# RP2350A.net
KiCad netlist of a schematic drawn in Altium Designer
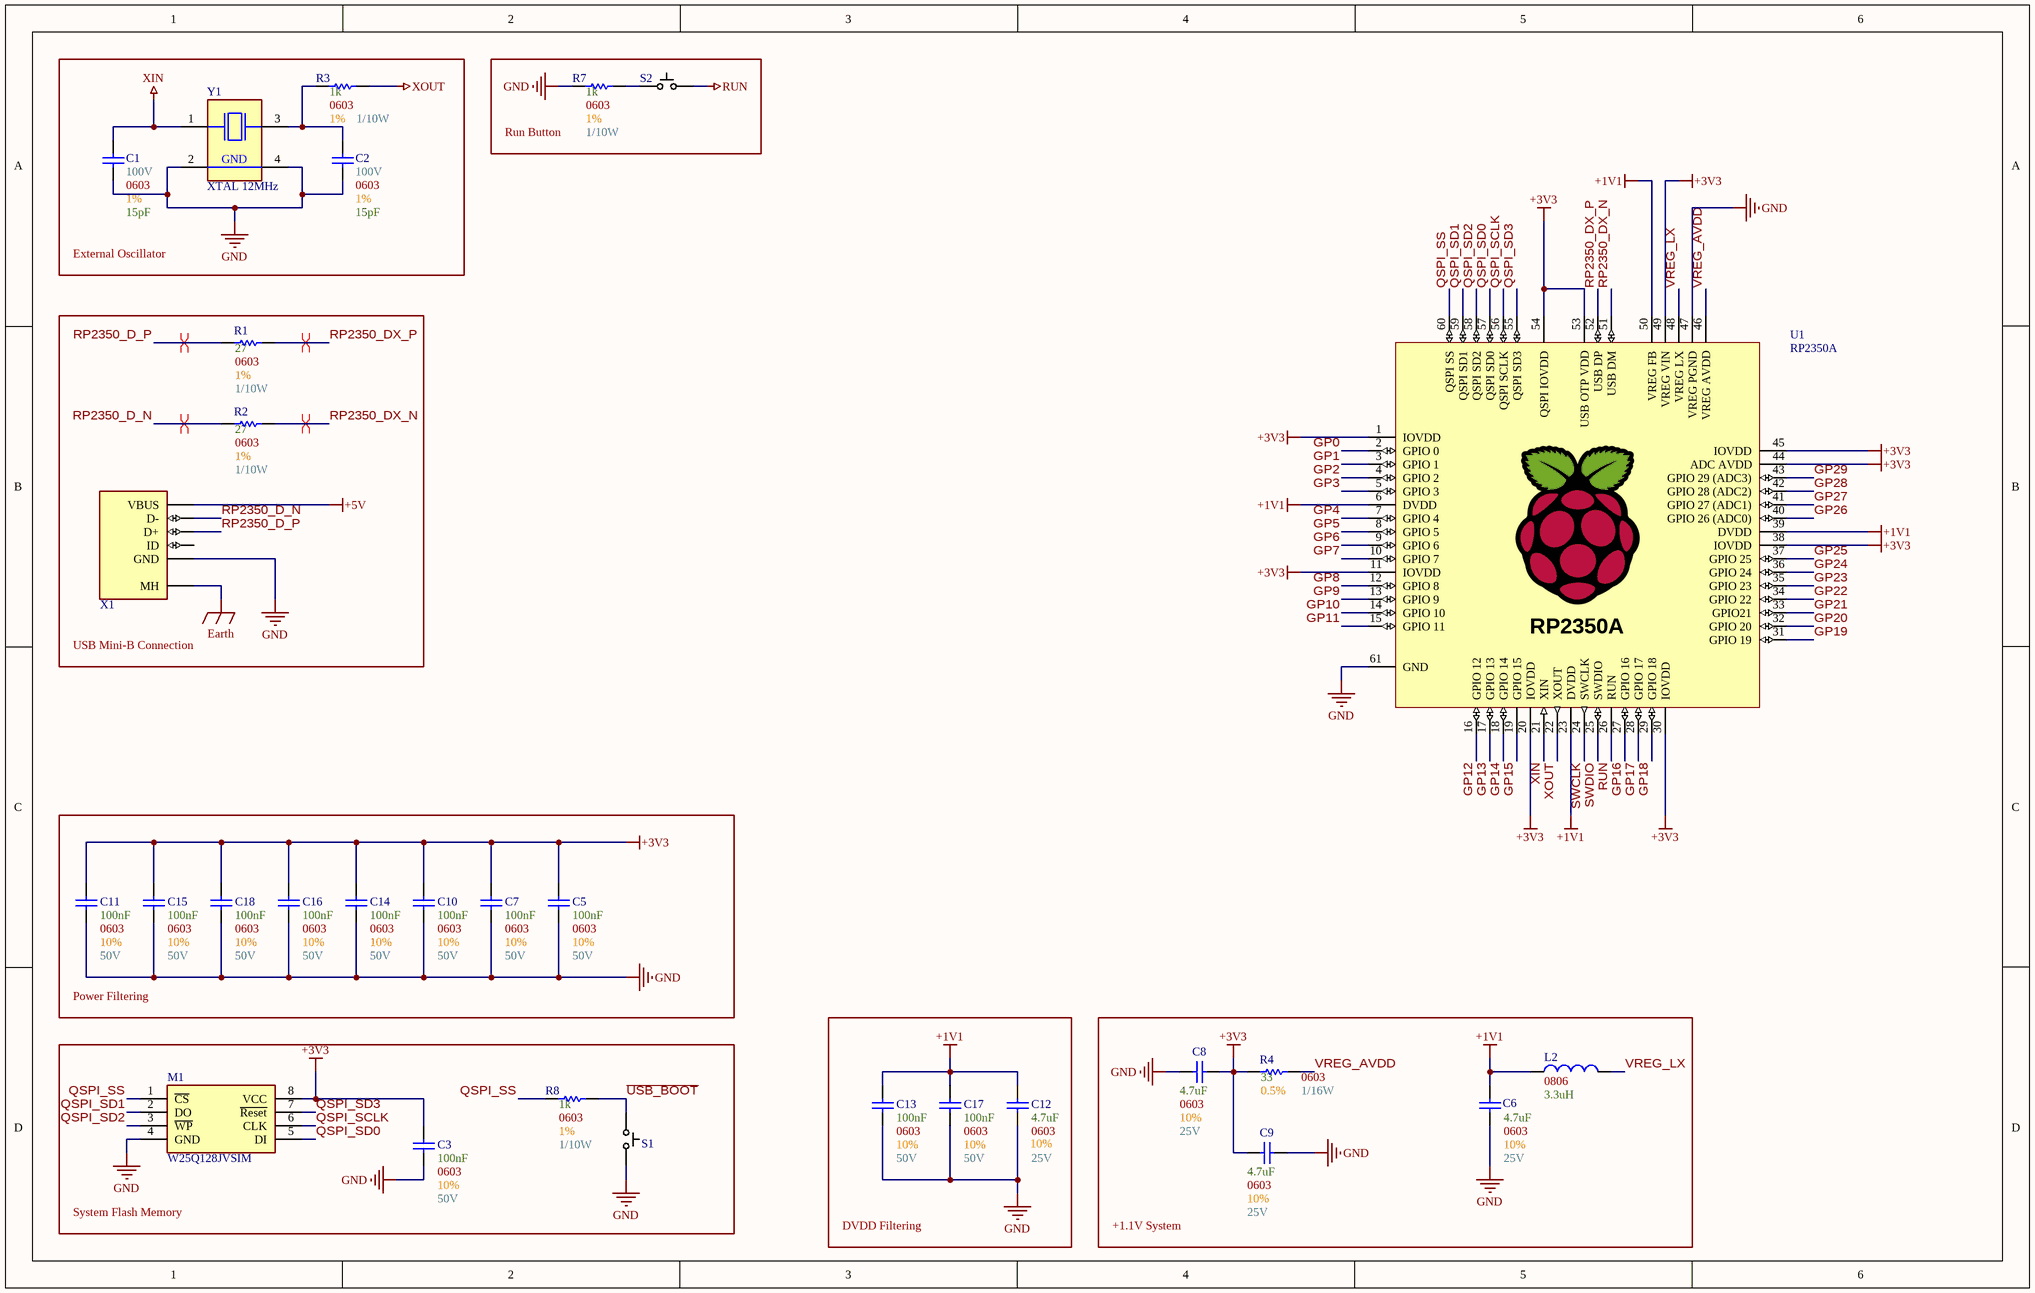
[diagram p0: RP2350A.SchDoc]

(export (version "E")
  (design (tool "Eeschema 10.0.6"))
  (components
    (comp (ref "C1")
      (value "[Cap] 0603 15pF 1% 100V")
      (footprint "[Cap] SMD 0603")
      (description "GCM1885C2A150FA16D")
      (fields
        (field (name "MAX VOLTAGE") "100V")
        (field (name "SIZE PACKAGE") "0603")
        (field (name "TOLERANCE") "1%")
        (field (name "CAPACITANCE") "15pF")
      )
      (libsource (lib "Capacitors") (part "[Cap] 0603 15pF 1% 100V"))
    )
    (comp (ref "C2")
      (value "[Cap] 0603 15pF 1% 100V")
      (footprint "[Cap] SMD 0603")
      (description "GCM1885C2A150FA16D")
      (fields
        (field (name "MAX VOLTAGE") "100V")
        (field (name "SIZE PACKAGE") "0603")
        (field (name "TOLERANCE") "1%")
        (field (name "CAPACITANCE") "15pF")
      )
      (libsource (lib "Capacitors") (part "[Cap] 0603 15pF 1% 100V"))
    )
    (comp (ref "C3")
      (value "[Cap] 0603 0.1uF 10% 50V")
      (footprint "[Cap] SMD 0603")
      (description "CL10B104KB8NNNC")
      (fields
        (field (name "MAX VOLTAGE") "50V")
        (field (name "SIZE PACKAGE") "0603")
        (field (name "TOLERANCE") "10%")
        (field (name "CAPACITANCE") "100nF")
      )
      (libsource (lib "Capacitors") (part "[Cap] 0603 0.1uF 10% 50V"))
    )
    (comp (ref "C5")
      (value "[Cap] 0603 0.1uF 10% 50V")
      (footprint "[Cap] SMD 0603")
      (description "CL10B104KB8NNNC")
      (fields
        (field (name "MAX VOLTAGE") "50V")
        (field (name "SIZE PACKAGE") "0603")
        (field (name "TOLERANCE") "10%")
        (field (name "CAPACITANCE") "100nF")
      )
      (libsource (lib "Capacitors") (part "[Cap] 0603 0.1uF 10% 50V"))
    )
    (comp (ref "C6")
      (value "[Cap] 0603 4.7uF 10% 25V")
      (footprint "[Cap] SMD 0603")
      (description "GRM188R61E475KE11D")
      (fields
        (field (name "MAX VOLTAGE") "25V")
        (field (name "SIZE PACKAGE") "0603")
        (field (name "TOLERANCE") "10%")
        (field (name "CAPACITANCE") "4.7uF")
      )
      (libsource (lib "Capacitors") (part "[Cap] 0603 4.7uF 10% 25V"))
    )
    (comp (ref "C7")
      (value "[Cap] 0603 0.1uF 10% 50V")
      (footprint "[Cap] SMD 0603")
      (description "CL10B104KB8NNNC")
      (fields
        (field (name "MAX VOLTAGE") "50V")
        (field (name "SIZE PACKAGE") "0603")
        (field (name "TOLERANCE") "10%")
        (field (name "CAPACITANCE") "100nF")
      )
      (libsource (lib "Capacitors") (part "[Cap] 0603 0.1uF 10% 50V"))
    )
    (comp (ref "C8")
      (value "[Cap] 0603 4.7uF 10% 25V")
      (footprint "[Cap] SMD 0603")
      (description "GRM188R61E475KE11D")
      (fields
        (field (name "MAX VOLTAGE") "25V")
        (field (name "SIZE PACKAGE") "0603")
        (field (name "TOLERANCE") "10%")
        (field (name "CAPACITANCE") "4.7uF")
      )
      (libsource (lib "Capacitors") (part "[Cap] 0603 4.7uF 10% 25V"))
    )
    (comp (ref "C9")
      (value "[Cap] 0603 4.7uF 10% 25V")
      (footprint "[Cap] SMD 0603")
      (description "GRM188R61E475KE11D")
      (fields
        (field (name "MAX VOLTAGE") "25V")
        (field (name "SIZE PACKAGE") "0603")
        (field (name "TOLERANCE") "10%")
        (field (name "CAPACITANCE") "4.7uF")
      )
      (libsource (lib "Capacitors") (part "[Cap] 0603 4.7uF 10% 25V"))
    )
    (comp (ref "C10")
      (value "[Cap] 0603 0.1uF 10% 50V")
      (footprint "[Cap] SMD 0603")
      (description "CL10B104KB8NNNC")
      (fields
        (field (name "MAX VOLTAGE") "50V")
        (field (name "SIZE PACKAGE") "0603")
        (field (name "TOLERANCE") "10%")
        (field (name "CAPACITANCE") "100nF")
      )
      (libsource (lib "Capacitors") (part "[Cap] 0603 0.1uF 10% 50V"))
    )
    (comp (ref "C11")
      (value "[Cap] 0603 0.1uF 10% 50V")
      (footprint "[Cap] SMD 0603")
      (description "CL10B104KB8NNNC")
      (fields
        (field (name "MAX VOLTAGE") "50V")
        (field (name "SIZE PACKAGE") "0603")
        (field (name "TOLERANCE") "10%")
        (field (name "CAPACITANCE") "100nF")
      )
      (libsource (lib "Capacitors") (part "[Cap] 0603 0.1uF 10% 50V"))
    )
    (comp (ref "C12")
      (value "[Cap] 0603 4.7uF 10% 25V")
      (footprint "[Cap] SMD 0603")
      (description "GRM188R61E475KE11D")
      (fields
        (field (name "MAX VOLTAGE") "25V")
        (field (name "SIZE PACKAGE") "0603")
        (field (name "TOLERANCE") "10%")
        (field (name "CAPACITANCE") "4.7uF")
      )
      (libsource (lib "Capacitors") (part "[Cap] 0603 4.7uF 10% 25V"))
    )
    (comp (ref "C13")
      (value "[Cap] 0603 0.1uF 10% 50V")
      (footprint "[Cap] SMD 0603")
      (description "CL10B104KB8NNNC")
      (fields
        (field (name "MAX VOLTAGE") "50V")
        (field (name "SIZE PACKAGE") "0603")
        (field (name "TOLERANCE") "10%")
        (field (name "CAPACITANCE") "100nF")
      )
      (libsource (lib "Capacitors") (part "[Cap] 0603 0.1uF 10% 50V"))
    )
    (comp (ref "C14")
      (value "[Cap] 0603 0.1uF 10% 50V")
      (footprint "[Cap] SMD 0603")
      (description "CL10B104KB8NNNC")
      (fields
        (field (name "MAX VOLTAGE") "50V")
        (field (name "SIZE PACKAGE") "0603")
        (field (name "TOLERANCE") "10%")
        (field (name "CAPACITANCE") "100nF")
      )
      (libsource (lib "Capacitors") (part "[Cap] 0603 0.1uF 10% 50V"))
    )
    (comp (ref "C15")
      (value "[Cap] 0603 0.1uF 10% 50V")
      (footprint "[Cap] SMD 0603")
      (description "CL10B104KB8NNNC")
      (fields
        (field (name "MAX VOLTAGE") "50V")
        (field (name "SIZE PACKAGE") "0603")
        (field (name "TOLERANCE") "10%")
        (field (name "CAPACITANCE") "100nF")
      )
      (libsource (lib "Capacitors") (part "[Cap] 0603 0.1uF 10% 50V"))
    )
    (comp (ref "C16")
      (value "[Cap] 0603 0.1uF 10% 50V")
      (footprint "[Cap] SMD 0603")
      (description "CL10B104KB8NNNC")
      (fields
        (field (name "MAX VOLTAGE") "50V")
        (field (name "SIZE PACKAGE") "0603")
        (field (name "TOLERANCE") "10%")
        (field (name "CAPACITANCE") "100nF")
      )
      (libsource (lib "Capacitors") (part "[Cap] 0603 0.1uF 10% 50V"))
    )
    (comp (ref "C17")
      (value "[Cap] 0603 0.1uF 10% 50V")
      (footprint "[Cap] SMD 0603")
      (description "CL10B104KB8NNNC")
      (fields
        (field (name "MAX VOLTAGE") "50V")
        (field (name "SIZE PACKAGE") "0603")
        (field (name "TOLERANCE") "10%")
        (field (name "CAPACITANCE") "100nF")
      )
      (libsource (lib "Capacitors") (part "[Cap] 0603 0.1uF 10% 50V"))
    )
    (comp (ref "C18")
      (value "[Cap] 0603 0.1uF 10% 50V")
      (footprint "[Cap] SMD 0603")
      (description "CL10B104KB8NNNC")
      (fields
        (field (name "MAX VOLTAGE") "50V")
        (field (name "SIZE PACKAGE") "0603")
        (field (name "TOLERANCE") "10%")
        (field (name "CAPACITANCE") "100nF")
      )
      (libsource (lib "Capacitors") (part "[Cap] 0603 0.1uF 10% 50V"))
    )
    (comp (ref "L2")
      (value "[3.3uH] SMD 0806 2.1A")
      (footprint "[Inductor] SMD 0806")
      (description "AOTA-B201610S3R3-101-T")
      (fields (field (name "PACKAGE") "0806") (field (name "INDUCTANCE") "3.3uH"))
      (libsource (lib "Inductors") (part "[3.3uH] SMD 0806 2.1A"))
    )
    (comp (ref "M1")
      (value "W25Q128JVSIM")
      (footprint "[Flash] 128MBit")
      (libsource (lib "Memory") (part "[Flash] 128MBit"))
    )
    (comp (ref "R1")
      (value "[27] SMD 0603 1% 1/10W")
      (footprint "[Res] SMD 0603")
      (description "MCT06030C2709FP500")
      (fields
        (field (name "WATTAGE") "1/10W")
        (field (name "TOLERANCE") "1%")
        (field (name "RESISTANCE") "27")
        (field (name "SIZE PACKAGE") "0603")
      )
      (libsource (lib "Resistors") (part "[27] SMD 0603 1% 1/10W"))
    )
    (comp (ref "R2")
      (value "[27] SMD 0603 1% 1/10W")
      (footprint "[Res] SMD 0603")
      (description "MCT06030C2709FP500")
      (fields
        (field (name "WATTAGE") "1/10W")
        (field (name "TOLERANCE") "1%")
        (field (name "RESISTANCE") "27")
        (field (name "SIZE PACKAGE") "0603")
      )
      (libsource (lib "Resistors") (part "[27] SMD 0603 1% 1/10W"))
    )
    (comp (ref "R3")
      (value "[1k] SMD 0603 1% 1/10W")
      (footprint "[Res] SMD 0603")
      (description "RMCF0603FT1K00")
      (fields
        (field (name "WATTAGE") "1/10W")
        (field (name "TOLERANCE") "1%")
        (field (name "RESISTANCE") "1k")
        (field (name "SIZE PACKAGE") "0603")
      )
      (libsource (lib "Resistors") (part "[1k] SMD 0603 1% 1/10W"))
    )
    (comp (ref "R4")
      (value "[33] SMD 0603 0.5% 1/16W")
      (footprint "[Res] SMD 0603")
      (description "RR0816Q-330-D")
      (fields
        (field (name "WATTAGE") "1/16W")
        (field (name "TOLERANCE") "0.5%")
        (field (name "RESISTANCE") "33")
        (field (name "SIZE PACKAGE") "0603")
      )
      (libsource (lib "Resistors") (part "[33] SMD 0603 0.5% 1/16W"))
    )
    (comp (ref "R7")
      (value "[1k] SMD 0603 1% 1/10W")
      (footprint "[Res] SMD 0603")
      (description "RMCF0603FT1K00")
      (fields
        (field (name "WATTAGE") "1/10W")
        (field (name "TOLERANCE") "1%")
        (field (name "RESISTANCE") "1k")
        (field (name "SIZE PACKAGE") "0603")
      )
      (libsource (lib "Resistors") (part "[1k] SMD 0603 1% 1/10W"))
    )
    (comp (ref "R8")
      (value "[1k] SMD 0603 1% 1/10W")
      (footprint "[Res] SMD 0603")
      (description "RMCF0603FT1K00")
      (fields
        (field (name "WATTAGE") "1/10W")
        (field (name "TOLERANCE") "1%")
        (field (name "RESISTANCE") "1k")
        (field (name "SIZE PACKAGE") "0603")
      )
      (libsource (lib "Resistors") (part "[1k] SMD 0603 1% 1/10W"))
    )
    (comp (ref "S1")
      (value "[SPST] SMD Pushbutton")
      (footprint "[SPST] SMD Pushbutton")
      (description "PTS815SJM250SMTRLFS")
      (libsource (lib "Switches") (part "[SPST] SMD Pushbutton"))
    )
    (comp (ref "S2")
      (value "[SPST] SMD Pushbutton")
      (footprint "[SPST] SMD Pushbutton")
      (description "PTS815SJM250SMTRLFS")
      (libsource (lib "Switches") (part "[SPST] SMD Pushbutton"))
    )
    (comp (ref "U1")
      (value "RP2350A")
      (footprint "[MCU] RP2350A")
      (description "QFN-60 Package")
      (libsource (lib "MCUs") (part "[MCU] RP2350A"))
    )
    (comp (ref "X1")
      (value "[USB] Type-B Mini")
      (footprint "[USB] Type-B Mini")
      (description "MUSB-05-S-B-SM-A-K-TR")
      (libsource (lib "Connectors") (part "[USB] Type-B Mini"))
    )
    (comp (ref "Y1")
      (value "XTAL 12MHz")
      (footprint "[Crystal] SMD 12MHz")
      (description "815-ABM8-272-T3")
      (libsource (lib "Crystals and Oscillators") (part "[Crystal] SMD 12MHz"))
    )
  )
  (nets
    (net (code "1") (name "+1V1") (class "Default")
      (node (ref "C12") (pin "2") (pinfunction "2_2") (pintype "passive"))
      (node (ref "C13") (pin "2") (pinfunction "2_2") (pintype "passive"))
      (node (ref "C17") (pin "2") (pinfunction "2_2") (pintype "passive"))
      (node (ref "C6") (pin "1") (pinfunction "1_1") (pintype "passive"))
      (node (ref "L2") (pin "1") (pinfunction "1_1") (pintype "passive"))
      (node (ref "U1") (pin "23") (pinfunction "DVDD_23") (pintype "power_in"))
      (node (ref "U1") (pin "39") (pinfunction "DVDD_39") (pintype "power_in"))
      (node (ref "U1") (pin "50") (pinfunction "VREG_FB_50") (pintype "power_in"))
      (node (ref "U1") (pin "6") (pinfunction "DVDD_6") (pintype "power_in"))
    )
    (net (code "2") (name "+3V3") (class "Default")
      (node (ref "C10") (pin "2") (pinfunction "2_2") (pintype "passive"))
      (node (ref "C11") (pin "2") (pinfunction "2_2") (pintype "passive"))
      (node (ref "C14") (pin "2") (pinfunction "2_2") (pintype "passive"))
      (node (ref "C15") (pin "2") (pinfunction "2_2") (pintype "passive"))
      (node (ref "C16") (pin "2") (pinfunction "2_2") (pintype "passive"))
      (node (ref "C18") (pin "2") (pinfunction "2_2") (pintype "passive"))
      (node (ref "C3") (pin "2") (pinfunction "2_2") (pintype "passive"))
      (node (ref "C5") (pin "2") (pinfunction "2_2") (pintype "passive"))
      (node (ref "C7") (pin "2") (pinfunction "2_2") (pintype "passive"))
      (node (ref "C8") (pin "1") (pinfunction "1_1") (pintype "passive"))
      (node (ref "C9") (pin "2") (pinfunction "2_2") (pintype "passive"))
      (node (ref "M1") (pin "8") (pinfunction "VCC_8") (pintype "passive"))
      (node (ref "R4") (pin "1") (pinfunction "1_1") (pintype "passive"))
      (node (ref "U1") (pin "1") (pinfunction "IOVDD_1") (pintype "power_in"))
      (node (ref "U1") (pin "11") (pinfunction "IOVDD_11") (pintype "power_in"))
      (node (ref "U1") (pin "20") (pinfunction "IOVDD_20") (pintype "power_in"))
      (node (ref "U1") (pin "30") (pinfunction "IOVDD_30") (pintype "power_in"))
      (node (ref "U1") (pin "38") (pinfunction "IOVDD_38") (pintype "power_in"))
      (node (ref "U1") (pin "44") (pinfunction "ADC_AVDD_44") (pintype "power_in"))
      (node (ref "U1") (pin "45") (pinfunction "IOVDD_45") (pintype "power_in"))
      (node (ref "U1") (pin "49") (pinfunction "VREG_VIN_49") (pintype "power_in"))
      (node (ref "U1") (pin "53") (pinfunction "USB_OTP_VDD_53") (pintype "power_in"))
      (node (ref "U1") (pin "54") (pinfunction "QSPI_IOVDD_54") (pintype "power_in"))
    )
    (net (code "3") (name "+5V") (class "Default")
      (node (ref "X1") (pin "1") (pinfunction "VBUS_1") (pintype "power_in"))
    )
    (net (code "4") (name "/GP0") (class "Default")
      (node (ref "U1") (pin "2") (pinfunction "GPIO_0_2") (pintype "bidirectional"))
    )
    (net (code "5") (name "/GP1") (class "Default")
      (node (ref "U1") (pin "3") (pinfunction "GPIO_1_3") (pintype "bidirectional"))
    )
    (net (code "6") (name "/GP2") (class "Default")
      (node (ref "U1") (pin "4") (pinfunction "GPIO_2_4") (pintype "bidirectional"))
    )
    (net (code "7") (name "/GP3") (class "Default")
      (node (ref "U1") (pin "5") (pinfunction "GPIO_3_5") (pintype "bidirectional"))
    )
    (net (code "8") (name "/GP4") (class "Default")
      (node (ref "U1") (pin "7") (pinfunction "GPIO_4_7") (pintype "bidirectional"))
    )
    (net (code "9") (name "/GP5") (class "Default")
      (node (ref "U1") (pin "8") (pinfunction "GPIO_5_8") (pintype "bidirectional"))
    )
    (net (code "10") (name "/GP6") (class "Default")
      (node (ref "U1") (pin "9") (pinfunction "GPIO_6_9") (pintype "bidirectional"))
    )
    (net (code "11") (name "/GP7") (class "Default")
      (node (ref "U1") (pin "10") (pinfunction "GPIO_7_10") (pintype "bidirectional"))
    )
    (net (code "12") (name "/GP8") (class "Default")
      (node (ref "U1") (pin "12") (pinfunction "GPIO_8_12") (pintype "bidirectional"))
    )
    (net (code "13") (name "/GP9") (class "Default")
      (node (ref "U1") (pin "13") (pinfunction "GPIO_9_13") (pintype "bidirectional"))
    )
    (net (code "14") (name "/GP10") (class "Default")
      (node (ref "U1") (pin "14") (pinfunction "GPIO_10_14") (pintype "bidirectional"))
    )
    (net (code "15") (name "/GP11") (class "Default")
      (node (ref "U1") (pin "15") (pinfunction "GPIO_11_15") (pintype "bidirectional"))
    )
    (net (code "16") (name "/GP12") (class "Default")
      (node (ref "U1") (pin "16") (pinfunction "GPIO_12_16") (pintype "bidirectional"))
    )
    (net (code "17") (name "/GP13") (class "Default")
      (node (ref "U1") (pin "17") (pinfunction "GPIO_13_17") (pintype "bidirectional"))
    )
    (net (code "18") (name "/GP14") (class "Default")
      (node (ref "U1") (pin "18") (pinfunction "GPIO_14_18") (pintype "bidirectional"))
    )
    (net (code "19") (name "/GP15") (class "Default")
      (node (ref "U1") (pin "19") (pinfunction "GPIO_15_19") (pintype "power_in"))
    )
    (net (code "20") (name "/GP16") (class "Default")
      (node (ref "U1") (pin "27") (pinfunction "GPIO_16_27") (pintype "bidirectional"))
    )
    (net (code "21") (name "/GP17") (class "Default")
      (node (ref "U1") (pin "28") (pinfunction "GPIO_17_28") (pintype "bidirectional"))
    )
    (net (code "22") (name "/GP18") (class "Default")
      (node (ref "U1") (pin "29") (pinfunction "GPIO_18_29") (pintype "bidirectional"))
    )
    (net (code "23") (name "/GP19") (class "Default")
      (node (ref "U1") (pin "31") (pinfunction "GPIO_19_31") (pintype "bidirectional"))
    )
    (net (code "24") (name "/GP20") (class "Default")
      (node (ref "U1") (pin "32") (pinfunction "GPIO_20_32") (pintype "bidirectional"))
    )
    (net (code "25") (name "/GP21") (class "Default")
      (node (ref "U1") (pin "33") (pinfunction "GPIO21_33") (pintype "bidirectional"))
    )
    (net (code "26") (name "/GP22") (class "Default")
      (node (ref "U1") (pin "34") (pinfunction "GPIO_22_34") (pintype "bidirectional"))
    )
    (net (code "27") (name "/GP23") (class "Default")
      (node (ref "U1") (pin "35") (pinfunction "GPIO_23_35") (pintype "bidirectional"))
    )
    (net (code "28") (name "/GP24") (class "Default")
      (node (ref "U1") (pin "36") (pinfunction "GPIO_24_36") (pintype "bidirectional"))
    )
    (net (code "29") (name "/GP25") (class "Default")
      (node (ref "U1") (pin "37") (pinfunction "GPIO_25_37") (pintype "bidirectional"))
    )
    (net (code "30") (name "/GP26") (class "Default")
      (node (ref "U1") (pin "40") (pinfunction "GPIO_26_(ADC0)_40") (pintype "bidirectional"))
    )
    (net (code "31") (name "/GP27") (class "Default")
      (node (ref "U1") (pin "41") (pinfunction "GPIO_27_(ADC1)_41") (pintype "bidirectional"))
    )
    (net (code "32") (name "/GP28") (class "Default")
      (node (ref "U1") (pin "42") (pinfunction "GPIO_28_(ADC2)_42") (pintype "bidirectional"))
    )
    (net (code "33") (name "/GP29") (class "Default")
      (node (ref "U1") (pin "43") (pinfunction "GPIO_29_(ADC3)_43") (pintype "bidirectional"))
    )
    (net (code "34") (name "/QSPI_SCLK") (class "Default")
      (node (ref "M1") (pin "6") (pinfunction "CLK_6") (pintype "passive"))
      (node (ref "U1") (pin "56") (pinfunction "QSPI_SCLK_56") (pintype "bidirectional"))
    )
    (net (code "35") (name "/QSPI_SD0") (class "Default")
      (node (ref "M1") (pin "5") (pinfunction "DI_5") (pintype "passive"))
      (node (ref "U1") (pin "57") (pinfunction "QSPI_SD0_57") (pintype "bidirectional"))
    )
    (net (code "36") (name "/QSPI_SD1") (class "Default")
      (node (ref "M1") (pin "2") (pinfunction "DO_2") (pintype "passive"))
      (node (ref "U1") (pin "59") (pinfunction "QSPI_SD1_59") (pintype "bidirectional"))
    )
    (net (code "37") (name "/QSPI_SD2") (class "Default")
      (node (ref "M1") (pin "3") (pinfunction "~{WP}_3") (pintype "passive"))
      (node (ref "U1") (pin "58") (pinfunction "QSPI_SD2_58") (pintype "bidirectional"))
    )
    (net (code "38") (name "/QSPI_SD3") (class "Default")
      (node (ref "M1") (pin "7") (pinfunction "~{Reset}_7") (pintype "passive"))
      (node (ref "U1") (pin "55") (pinfunction "QSPI_SD3_55") (pintype "bidirectional"))
    )
    (net (code "39") (name "/QSPI_SS") (class "Default")
      (node (ref "M1") (pin "1") (pinfunction "~{CS}_1") (pintype "passive"))
      (node (ref "R8") (pin "1") (pinfunction "1_1") (pintype "passive"))
      (node (ref "U1") (pin "60") (pinfunction "QSPI_SS_60") (pintype "bidirectional"))
    )
    (net (code "40") (name "/RP2350_DX_N") (class "Default")
      (node (ref "R2") (pin "2") (pinfunction "2_2") (pintype "passive"))
      (node (ref "U1") (pin "51") (pinfunction "USB_DM_51") (pintype "bidirectional"))
    )
    (net (code "41") (name "/RP2350_DX_P") (class "Default")
      (node (ref "R1") (pin "2") (pinfunction "2_2") (pintype "passive"))
      (node (ref "U1") (pin "52") (pinfunction "USB_DP_52") (pintype "bidirectional"))
    )
    (net (code "42") (name "/RP2350_D_N") (class "Default")
      (node (ref "R2") (pin "1") (pinfunction "1_1") (pintype "passive"))
      (node (ref "X1") (pin "2") (pinfunction "D-_2") (pintype "bidirectional"))
    )
    (net (code "43") (name "/RP2350_D_P") (class "Default")
      (node (ref "R1") (pin "1") (pinfunction "1_1") (pintype "passive"))
      (node (ref "X1") (pin "3") (pinfunction "D+_3") (pintype "bidirectional"))
    )
    (net (code "44") (name "/SWCLK") (class "Default")
      (node (ref "U1") (pin "24") (pinfunction "SWCLK_24") (pintype "output"))
    )
    (net (code "45") (name "/SWDIO") (class "Default")
      (node (ref "U1") (pin "25") (pinfunction "SWDIO_25") (pintype "bidirectional"))
    )
    (net (code "46") (name "/VREG_AVDD") (class "Default")
      (node (ref "R4") (pin "2") (pinfunction "2_2") (pintype "passive"))
      (node (ref "U1") (pin "46") (pinfunction "VREG_AVDD_46") (pintype "power_in"))
    )
    (net (code "47") (name "/VREG_LX") (class "Default")
      (node (ref "L2") (pin "2") (pinfunction "2_2") (pintype "passive"))
      (node (ref "U1") (pin "48") (pinfunction "VREG_LX_48") (pintype "power_in"))
    )
    (net (code "48") (name "/~{USB_BOOT}") (class "Default")
      (node (ref "R8") (pin "2") (pinfunction "2_2") (pintype "passive"))
      (node (ref "S1") (pin "1") (pintype "power_in"))
    )
    (net (code "49") (name "Earth") (class "Default")
      (node (ref "X1") (pin "MH") (pinfunction "MH_MH") (pintype "power_in"))
    )
    (net (code "50") (name "GND") (class "Default")
      (node (ref "C1") (pin "1") (pinfunction "1_1") (pintype "passive"))
      (node (ref "C10") (pin "1") (pinfunction "1_1") (pintype "passive"))
      (node (ref "C11") (pin "1") (pinfunction "1_1") (pintype "passive"))
      (node (ref "C12") (pin "1") (pinfunction "1_1") (pintype "passive"))
      (node (ref "C13") (pin "1") (pinfunction "1_1") (pintype "passive"))
      (node (ref "C14") (pin "1") (pinfunction "1_1") (pintype "passive"))
      (node (ref "C15") (pin "1") (pinfunction "1_1") (pintype "passive"))
      (node (ref "C16") (pin "1") (pinfunction "1_1") (pintype "passive"))
      (node (ref "C17") (pin "1") (pinfunction "1_1") (pintype "passive"))
      (node (ref "C18") (pin "1") (pinfunction "1_1") (pintype "passive"))
      (node (ref "C2") (pin "1") (pinfunction "1_1") (pintype "passive"))
      (node (ref "C3") (pin "1") (pinfunction "1_1") (pintype "passive"))
      (node (ref "C5") (pin "1") (pinfunction "1_1") (pintype "passive"))
      (node (ref "C6") (pin "2") (pinfunction "2_2") (pintype "passive"))
      (node (ref "C7") (pin "1") (pinfunction "1_1") (pintype "passive"))
      (node (ref "C8") (pin "2") (pinfunction "2_2") (pintype "passive"))
      (node (ref "C9") (pin "1") (pinfunction "1_1") (pintype "passive"))
      (node (ref "M1") (pin "4") (pinfunction "GND_4") (pintype "passive"))
      (node (ref "R7") (pin "1") (pinfunction "1_1") (pintype "passive"))
      (node (ref "S1") (pin "2") (pintype "power_in"))
      (node (ref "U1") (pin "47") (pinfunction "VREG_PGND_47") (pintype "power_in"))
      (node (ref "U1") (pin "61") (pinfunction "GND_61") (pintype "power_in"))
      (node (ref "X1") (pin "5") (pinfunction "GND_5") (pintype "power_in"))
      (node (ref "Y1") (pin "2") (pinfunction "GND_2") (pintype "power_in"))
      (node (ref "Y1") (pin "4") (pinfunction "GND_4") (pintype "power_in"))
    )
    (net (code "51") (name "Net-(R7-Pad2)") (class "Default")
      (node (ref "R7") (pin "2") (pinfunction "2_2") (pintype "passive"))
      (node (ref "S2") (pin "1") (pintype "power_in"))
    )
    (net (code "52") (name "Net-(Y1-XTAL2)") (class "Default")
      (node (ref "C2") (pin "2") (pinfunction "2_2") (pintype "passive"))
      (node (ref "R3") (pin "1") (pinfunction "1_1") (pintype "passive"))
      (node (ref "Y1") (pin "3") (pinfunction "XTAL2_3") (pintype "power_in"))
    )
    (net (code "53") (name "RUN") (class "Default")
      (node (ref "S2") (pin "2") (pintype "power_in"))
      (node (ref "U1") (pin "26") (pinfunction "RUN_26") (pintype "passive"))
    )
    (net (code "54") (name "XIN") (class "Default")
      (node (ref "C1") (pin "2") (pinfunction "2_2") (pintype "passive"))
      (node (ref "U1") (pin "21") (pinfunction "XIN_21") (pintype "input"))
      (node (ref "Y1") (pin "1") (pinfunction "XTAL1_1") (pintype "power_in"))
    )
    (net (code "55") (name "XOUT") (class "Default")
      (node (ref "R3") (pin "2") (pinfunction "2_2") (pintype "passive"))
      (node (ref "U1") (pin "22") (pinfunction "XOUT_22") (pintype "output"))
    )
    (net (code "56") (name "unconnected-(X1-ID-Pad4)") (class "Default")
      (node (ref "X1") (pin "4") (pinfunction "ID_4") (pintype "bidirectional"))
    )
  )
)
